# OLED_I2C_NANO.net
KiCad netlist of a schematic drawn in EAGLE
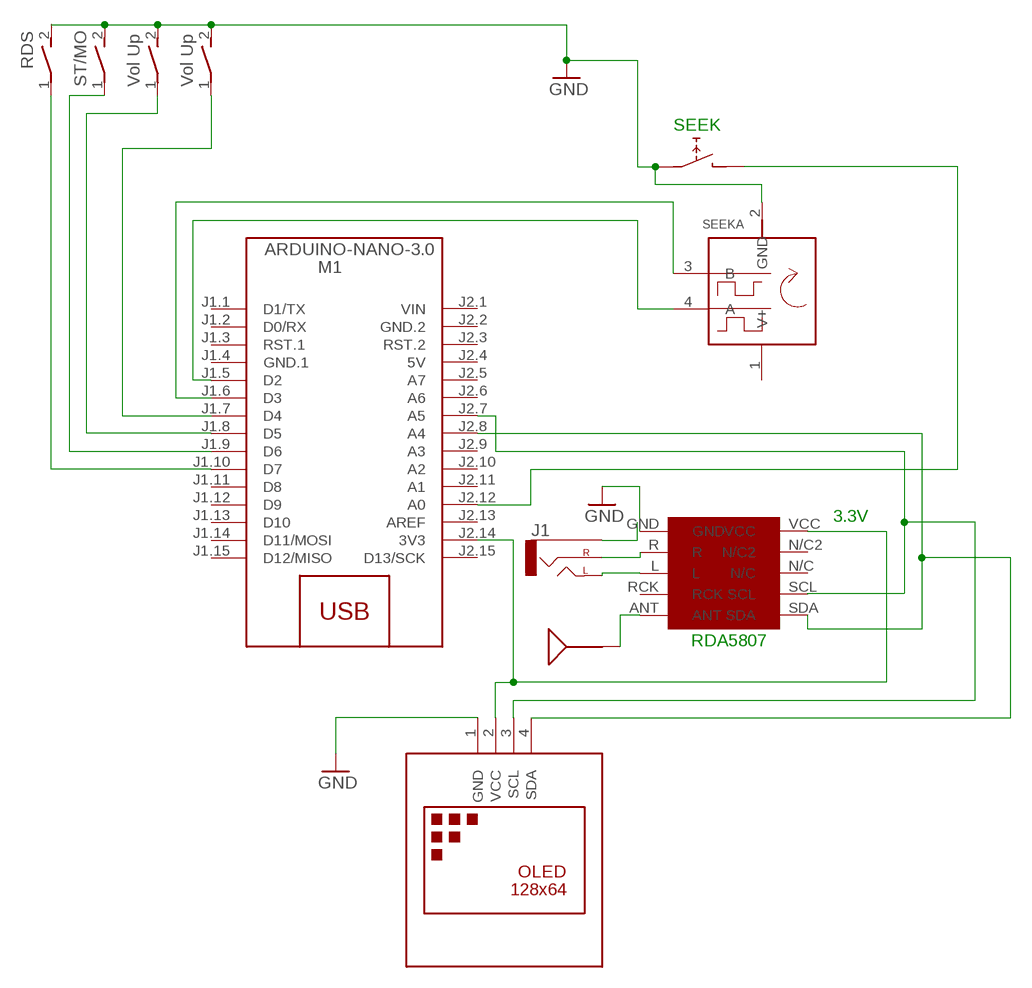
[diagram p0: schematic, sheet 1]

(export (version "E")
  (design (tool "Eeschema 10.0.6"))
  (components
    (comp (ref "A1")
      (value "ANTENNA-2.4GHZ-3.2X1.6MM")
      (footprint "eagle-import:ANT-2.4GHZ-3.2X1.6X1.2MM")
      (libsource (lib "eagle-import") (part "ANTENNA-2.4GHZ-3.2X1.6MM"))
    )
    (comp (ref "J1")
      (value "AUDIO_JACK_2.5MM_2.5MM")
      (footprint "eagle-import:STEREOJACK2.5MM_STEREOJACK2.5MM")
      (libsource (lib "eagle-import") (part "AUDIO_JACK_2.5MM_2.5MM"))
    )
    (comp (ref "M1")
      (value "ARDUINO-NANO-3.0")
      (footprint "eagle-import:ARDUINO-NANO-3.0")
      (libsource (lib "eagle-import") (part "ARDUINO-NANO-3.0"))
    )
    (comp (ref "S1")
      (value "Vol Up")
      (footprint "eagle-import:DS-01")
      (libsource (lib "eagle-import") (part "DS01E"))
    )
    (comp (ref "S4")
      (value "Vol Up")
      (footprint "eagle-import:DS-01")
      (libsource (lib "eagle-import") (part "DS01E"))
    )
    (comp (ref "S5")
      (value "ST/MO")
      (footprint "eagle-import:DS-01")
      (libsource (lib "eagle-import") (part "DS01E"))
    )
    (comp (ref "S6")
      (value "RDS")
      (footprint "eagle-import:DS-01")
      (libsource (lib "eagle-import") (part "DS01E"))
    )
    (comp (ref "SEEK")
      (value "62P16-HX")
      (footprint "eagle-import:62P")
      (libsource (lib "eagle-import") (part "62PX16-H"))
    )
    (comp (ref "U$1")
      (value "RDA")
      (footprint "eagle-import:RDA")
      (libsource (lib "eagle-import") (part "RDA"))
    )
    (comp (ref "U$2")
      (value "DISPLAY-OLED-128X64-I2C")
      (footprint "eagle-import:DISPLAY-OLED-128X64-I2C")
      (libsource (lib "eagle-import") (part "DISPLAY-OLED-128X64-I2C"))
    )
  )
  (nets
    (net (code "1") (name "/5V") (class "Default")
      (node (ref "M1") (pin "J2.4") (pinfunction "5V_J2.4") (pintype "power_in"))
    )
    (net (code "2") (name "/GND.1") (class "Default")
      (node (ref "M1") (pin "J1.4") (pinfunction "GND.1_J1.4") (pintype "power_in"))
    )
    (net (code "3") (name "/GND.2") (class "Default")
      (node (ref "M1") (pin "J2.2") (pinfunction "GND.2_J2.2") (pintype "power_in"))
    )
    (net (code "4") (name "/V+") (class "Default")
      (node (ref "SEEK") (pin "1") (pinfunction "V+_1") (pintype "power_in"))
    )
    (net (code "5") (name "/VIN") (class "Default")
      (node (ref "M1") (pin "J2.1") (pinfunction "VIN_J2.1") (pintype "power_in"))
    )
    (net (code "6") (name "GND") (class "Default")
      (node (ref "S1") (pin "2") (pinfunction "2_2") (pintype "passive"))
      (node (ref "S4") (pin "2") (pinfunction "2_2") (pintype "passive"))
      (node (ref "S5") (pin "2") (pinfunction "2_2") (pintype "passive"))
      (node (ref "S6") (pin "2") (pinfunction "2_2") (pintype "passive"))
      (node (ref "SEEK") (pin "2") (pinfunction "GND_2") (pintype "power_in"))
      (node (ref "SEEK") (pin "5") (pinfunction "D_5") (pintype "passive"))
      (node (ref "U$1") (pin "GND") (pinfunction "GND_GND") (pintype "power_in"))
      (node (ref "U$2") (pin "1") (pinfunction "GND_1") (pintype "power_in"))
    )
    (net (code "7") (name "Net-(A1-SIGNAL)") (class "Default")
      (node (ref "A1") (pin "FEED") (pinfunction "SIGNAL_FEED") (pintype "bidirectional"))
      (node (ref "U$1") (pin "ANT") (pinfunction "ANT_ANT") (pintype "input"))
    )
    (net (code "8") (name "Net-(J1-LEFT)") (class "Default")
      (node (ref "J1") (pin "SHIELD") (pinfunction "LEFT_SHIELD") (pintype "bidirectional"))
      (node (ref "U$1") (pin "L") (pinfunction "L_L") (pintype "output"))
    )
    (net (code "9") (name "Net-(J1-RIGHT)") (class "Default")
      (node (ref "J1") (pin "TIP") (pinfunction "RIGHT_TIP") (pintype "bidirectional"))
      (node (ref "U$1") (pin "R") (pinfunction "R_R") (pintype "output"))
    )
    (net (code "10") (name "Net-(M1-3V3)") (class "Default")
      (node (ref "M1") (pin "J2.14") (pinfunction "3V3_J2.14") (pintype "power_in"))
      (node (ref "U$1") (pin "VCC") (pinfunction "VCC_VCC") (pintype "power_in"))
      (node (ref "U$2") (pin "2") (pinfunction "VCC_2") (pintype "power_in"))
    )
    (net (code "11") (name "Net-(M1-A0)") (class "Default")
      (node (ref "M1") (pin "J2.12") (pinfunction "A0_J2.12") (pintype "bidirectional"))
      (node (ref "SEEK") (pin "6") (pinfunction "E_6") (pintype "passive"))
    )
    (net (code "12") (name "Net-(M1-A4)") (class "Default")
      (node (ref "M1") (pin "J2.8") (pinfunction "A4_J2.8") (pintype "bidirectional"))
      (node (ref "U$1") (pin "SDA") (pinfunction "SDA_SDA") (pintype "bidirectional"))
      (node (ref "U$2") (pin "4") (pinfunction "SDA_4") (pintype "bidirectional"))
    )
    (net (code "13") (name "Net-(M1-A5)") (class "Default")
      (node (ref "M1") (pin "J2.7") (pinfunction "A5_J2.7") (pintype "bidirectional"))
      (node (ref "U$1") (pin "SCL") (pinfunction "SCL_SCL") (pintype "bidirectional"))
      (node (ref "U$2") (pin "3") (pinfunction "SCL_3") (pintype "bidirectional"))
    )
    (net (code "14") (name "Net-(M1-D2)") (class "Default")
      (node (ref "M1") (pin "J1.5") (pinfunction "D2_J1.5") (pintype "bidirectional"))
      (node (ref "SEEK") (pin "4") (pinfunction "A_4") (pintype "bidirectional"))
    )
    (net (code "15") (name "Net-(M1-D3)") (class "Default")
      (node (ref "M1") (pin "J1.6") (pinfunction "D3_J1.6") (pintype "bidirectional"))
      (node (ref "SEEK") (pin "3") (pinfunction "B_3") (pintype "bidirectional"))
    )
    (net (code "16") (name "Net-(M1-D4)") (class "Default")
      (node (ref "M1") (pin "J1.7") (pinfunction "D4_J1.7") (pintype "bidirectional"))
      (node (ref "S1") (pin "1") (pinfunction "1_1") (pintype "passive"))
    )
    (net (code "17") (name "Net-(M1-D5)") (class "Default")
      (node (ref "M1") (pin "J1.8") (pinfunction "D5_J1.8") (pintype "bidirectional"))
      (node (ref "S4") (pin "1") (pinfunction "1_1") (pintype "passive"))
    )
    (net (code "18") (name "Net-(M1-D6)") (class "Default")
      (node (ref "M1") (pin "J1.9") (pinfunction "D6_J1.9") (pintype "bidirectional"))
      (node (ref "S5") (pin "1") (pinfunction "1_1") (pintype "passive"))
    )
    (net (code "19") (name "Net-(M1-D7)") (class "Default")
      (node (ref "M1") (pin "J1.10") (pinfunction "D7_J1.10") (pintype "bidirectional"))
      (node (ref "S6") (pin "1") (pinfunction "1_1") (pintype "passive"))
    )
    (net (code "20") (name "unconnected-(J1-SLEEVE-PadRING1)") (class "Default")
      (node (ref "J1") (pin "RING1") (pinfunction "SLEEVE_RING1") (pintype "bidirectional"))
    )
    (net (code "21") (name "unconnected-(M1-A1-PadJ2.11)") (class "Default")
      (node (ref "M1") (pin "J2.11") (pinfunction "A1_J2.11") (pintype "bidirectional"))
    )
    (net (code "22") (name "unconnected-(M1-A2-PadJ2.10)") (class "Default")
      (node (ref "M1") (pin "J2.10") (pinfunction "A2_J2.10") (pintype "bidirectional"))
    )
    (net (code "23") (name "unconnected-(M1-A3-PadJ2.9)") (class "Default")
      (node (ref "M1") (pin "J2.9") (pinfunction "A3_J2.9") (pintype "bidirectional"))
    )
    (net (code "24") (name "unconnected-(M1-A6-PadJ2.6)") (class "Default")
      (node (ref "M1") (pin "J2.6") (pinfunction "A6_J2.6") (pintype "bidirectional"))
    )
    (net (code "25") (name "unconnected-(M1-A7-PadJ2.5)") (class "Default")
      (node (ref "M1") (pin "J2.5") (pinfunction "A7_J2.5") (pintype "bidirectional"))
    )
    (net (code "26") (name "unconnected-(M1-AREF-PadJ2.13)") (class "Default")
      (node (ref "M1") (pin "J2.13") (pinfunction "AREF_J2.13") (pintype "bidirectional"))
    )
    (net (code "27") (name "unconnected-(M1-D0{slash}RX-PadJ1.2)") (class "Default")
      (node (ref "M1") (pin "J1.2") (pinfunction "D0/RX_J1.2") (pintype "bidirectional"))
    )
    (net (code "28") (name "unconnected-(M1-D1{slash}TX-PadJ1.1)") (class "Default")
      (node (ref "M1") (pin "J1.1") (pinfunction "D1/TX_J1.1") (pintype "bidirectional"))
    )
    (net (code "29") (name "unconnected-(M1-D8-PadJ1.11)") (class "Default")
      (node (ref "M1") (pin "J1.11") (pinfunction "D8_J1.11") (pintype "bidirectional"))
    )
    (net (code "30") (name "unconnected-(M1-D9-PadJ1.12)") (class "Default")
      (node (ref "M1") (pin "J1.12") (pinfunction "D9_J1.12") (pintype "bidirectional"))
    )
    (net (code "31") (name "unconnected-(M1-D10-PadJ1.13)") (class "Default")
      (node (ref "M1") (pin "J1.13") (pinfunction "D10_J1.13") (pintype "bidirectional"))
    )
    (net (code "32") (name "unconnected-(M1-D11{slash}MOSI-PadJ1.14)") (class "Default")
      (node (ref "M1") (pin "J1.14") (pinfunction "D11/MOSI_J1.14") (pintype "bidirectional"))
    )
    (net (code "33") (name "unconnected-(M1-D12{slash}MISO-PadJ1.15)") (class "Default")
      (node (ref "M1") (pin "J1.15") (pinfunction "D12/MISO_J1.15") (pintype "bidirectional"))
    )
    (net (code "34") (name "unconnected-(M1-D13{slash}SCK-PadJ2.15)") (class "Default")
      (node (ref "M1") (pin "J2.15") (pinfunction "D13/SCK_J2.15") (pintype "bidirectional"))
    )
    (net (code "35") (name "unconnected-(M1-RST.1-PadJ1.3)") (class "Default")
      (node (ref "M1") (pin "J1.3") (pinfunction "RST.1_J1.3") (pintype "bidirectional"))
    )
    (net (code "36") (name "unconnected-(M1-RST.2-PadJ2.3)") (class "Default")
      (node (ref "M1") (pin "J2.3") (pinfunction "RST.2_J2.3") (pintype "bidirectional"))
    )
    (net (code "37") (name "unconnected-(U$1-PadN{slash}C)") (class "Default")
      (node (ref "U$1") (pin "N/C") (pinfunction "N/C_N/C") (pintype "passive"))
    )
    (net (code "38") (name "unconnected-(U$1-PadN{slash}C2)") (class "Default")
      (node (ref "U$1") (pin "N/C2") (pinfunction "N/C2_N/C2") (pintype "passive"))
    )
    (net (code "39") (name "unconnected-(U$1-PadRCK)") (class "Default")
      (node (ref "U$1") (pin "RCK") (pinfunction "RCK_RCK") (pintype "bidirectional"))
    )
  )
)
